# Gate_Driver_Supply.net
KiCad netlist of a schematic drawn in Altium Designer
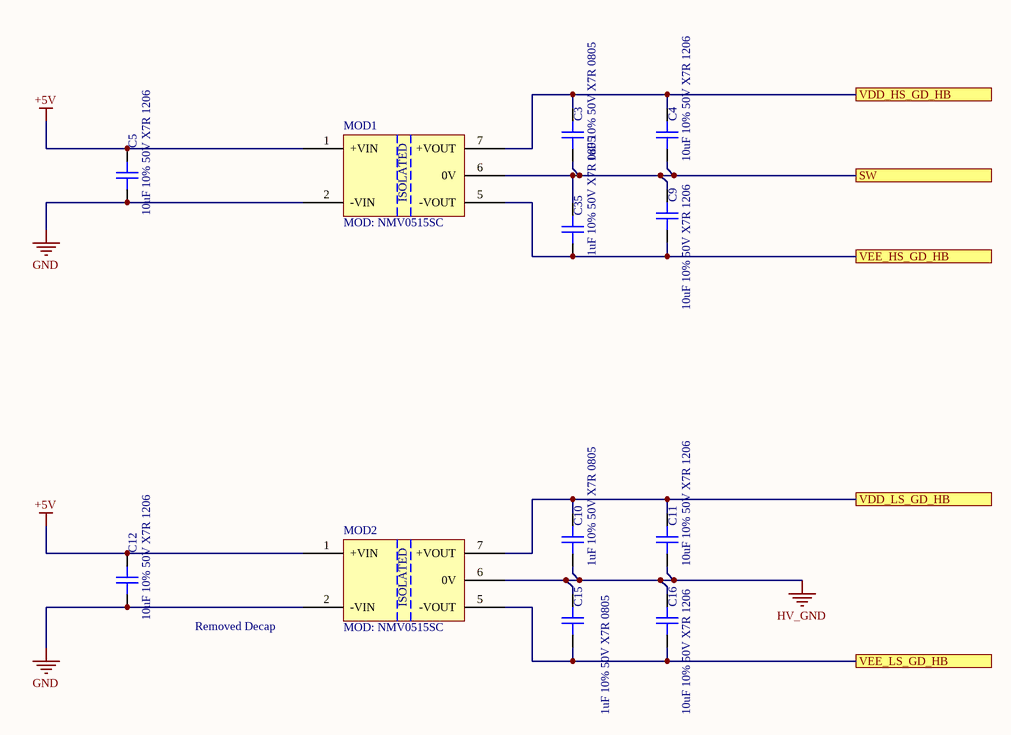
[diagram p0: Gate_Driver_Supply.SchDoc]

(export (version "E")
  (design (tool "Eeschema 10.0.6"))
  (components
    (comp (ref "C3")
      (value "1uF 10% 50V X7R 0805")
      (footprint "CAPC2012X10N")
      (fields
        (field (name "MANUFACTURER PART NUMBER") "C2012X7R1H105K125AB")
        (field (name "MANUFACTURER") "TDK")
      )
      (libsource (lib "EMEA- E-Tech Racing- I'Escola d'Enginyeria de Barcelona Est") (part "68pF 10 630V C0G 0805"))
    )
    (comp (ref "C4")
      (value "10uF 10% 50V X7R 1206")
      (footprint "CAPC3216X18N")
      (fields
        (field (name "MANUFACTURER PART NUMBER") "C3216X7R1H106K160AC")
        (field (name "MANUFACTURER") "TDK")
      )
      (libsource (lib "EMEA- E-Tech Racing- I'Escola d'Enginyeria de Barcelona Est") (part "68pF 10 630V C0G 0805"))
    )
    (comp (ref "C5")
      (value "10uF 10% 50V X7R 1206")
      (footprint "CAPC3216X18N")
      (fields
        (field (name "MANUFACTURER PART NUMBER") "C3216X7R1H106K160AC")
        (field (name "MANUFACTURER") "TDK")
      )
      (libsource (lib "EMEA- E-Tech Racing- I'Escola d'Enginyeria de Barcelona Est") (part "68pF 10 630V C0G 0805"))
    )
    (comp (ref "C9")
      (value "10uF 10% 50V X7R 1206")
      (footprint "CAPC3216X18N")
      (fields
        (field (name "MANUFACTURER PART NUMBER") "C3216X7R1H106K160AC")
        (field (name "MANUFACTURER") "TDK")
      )
      (libsource (lib "EMEA- E-Tech Racing- I'Escola d'Enginyeria de Barcelona Est") (part "68pF 10 630V C0G 0805"))
    )
    (comp (ref "C10")
      (value "1uF 10% 50V X7R 0805")
      (footprint "CAPC2012X10N")
      (fields
        (field (name "MANUFACTURER PART NUMBER") "C2012X7R1H105K125AB")
        (field (name "MANUFACTURER") "TDK")
      )
      (libsource (lib "EMEA- E-Tech Racing- I'Escola d'Enginyeria de Barcelona Est") (part "68pF 10 630V C0G 0805"))
    )
    (comp (ref "C11")
      (value "10uF 10% 50V X7R 1206")
      (footprint "CAPC3216X18N")
      (fields
        (field (name "MANUFACTURER PART NUMBER") "C3216X7R1H106K160AC")
        (field (name "MANUFACTURER") "TDK")
      )
      (libsource (lib "EMEA- E-Tech Racing- I'Escola d'Enginyeria de Barcelona Est") (part "68pF 10 630V C0G 0805"))
    )
    (comp (ref "C12")
      (value "10uF 10% 50V X7R 1206")
      (footprint "CAPC3216X18N")
      (fields
        (field (name "MANUFACTURER PART NUMBER") "C3216X7R1H106K160AC")
        (field (name "MANUFACTURER") "TDK")
      )
      (libsource (lib "EMEA- E-Tech Racing- I'Escola d'Enginyeria de Barcelona Est") (part "68pF 10 630V C0G 0805"))
    )
    (comp (ref "C15")
      (value "1uF 10% 50V X7R 0805")
      (footprint "CAPC2012X10N")
      (fields
        (field (name "MANUFACTURER PART NUMBER") "C2012X7R1H105K125AB")
        (field (name "MANUFACTURER") "TDK")
      )
      (libsource (lib "EMEA- E-Tech Racing- I'Escola d'Enginyeria de Barcelona Est") (part "68pF 10 630V C0G 0805"))
    )
    (comp (ref "C16")
      (value "10uF 10% 50V X7R 1206")
      (footprint "CAPC3216X18N")
      (fields
        (field (name "MANUFACTURER PART NUMBER") "C3216X7R1H106K160AC")
        (field (name "MANUFACTURER") "TDK")
      )
      (libsource (lib "EMEA- E-Tech Racing- I'Escola d'Enginyeria de Barcelona Est") (part "68pF 10 630V C0G 0805"))
    )
    (comp (ref "C35")
      (value "1uF 10% 50V X7R 0805")
      (footprint "CAPC2012X10N")
      (fields
        (field (name "MANUFACTURER PART NUMBER") "C2012X7R1H105K125AB")
        (field (name "MANUFACTURER") "TDK")
      )
      (libsource (lib "EMEA- E-Tech Racing- I'Escola d'Enginyeria de Barcelona Est") (part "68pF 10 630V C0G 0805"))
    )
    (comp (ref "MOD1")
      (value "MOD: NMV0515SC")
      (footprint "MOD: NMV0515SC")
      (description "Module DC-DC 5VIN 2-OUT 15V/-15V 0.033A/-0.033A 1W 5-Pin SIP Tube")
      (fields
        (field (name "MANUFACTURER") "Murata Power Solutions")
        (field (name "MANUFACTURER PART NUMBER") "NMV0515SC")
      )
      (libsource (lib "EMEA- E-Tech Racing- I'Escola d'Enginyeria de Barcelona Est") (part "MOD{colon} NMV0515SC"))
    )
    (comp (ref "MOD2")
      (value "MOD: NMV0515SC")
      (footprint "MOD: NMV0515SC")
      (description "Module DC-DC 5VIN 2-OUT 15V/-15V 0.033A/-0.033A 1W 5-Pin SIP Tube")
      (fields
        (field (name "MANUFACTURER") "Murata Power Solutions")
        (field (name "MANUFACTURER PART NUMBER") "NMV0515SC")
      )
      (libsource (lib "EMEA- E-Tech Racing- I'Escola d'Enginyeria de Barcelona Est") (part "MOD{colon} NMV0515SC"))
    )
  )
  (nets
    (net (code "1") (name "+5V") (class "Default")
      (node (ref "C12") (pin "2") (pinfunction "2_2") (pintype "passive"))
      (node (ref "C5") (pin "2") (pinfunction "2_2") (pintype "passive"))
      (node (ref "MOD1") (pin "1") (pinfunction "+VIN_1") (pintype "passive"))
      (node (ref "MOD2") (pin "1") (pinfunction "+VIN_1") (pintype "passive"))
    )
    (net (code "2") (name "/SW") (class "Default")
      (node (ref "C3") (pin "1") (pinfunction "1_1") (pintype "passive"))
      (node (ref "C35") (pin "2") (pinfunction "2_2") (pintype "passive"))
      (node (ref "C4") (pin "1") (pinfunction "1_1") (pintype "passive"))
      (node (ref "C9") (pin "2") (pinfunction "2_2") (pintype "passive"))
      (node (ref "MOD1") (pin "6") (pinfunction "0V_6") (pintype "passive"))
    )
    (net (code "3") (name "/VDD_HS_GD_HB") (class "Default")
      (node (ref "C3") (pin "2") (pinfunction "2_2") (pintype "passive"))
      (node (ref "C4") (pin "2") (pinfunction "2_2") (pintype "passive"))
      (node (ref "MOD1") (pin "7") (pinfunction "+VOUT_7") (pintype "passive"))
    )
    (net (code "4") (name "/VDD_LS_GD_HB") (class "Default")
      (node (ref "C10") (pin "2") (pinfunction "2_2") (pintype "passive"))
      (node (ref "C11") (pin "2") (pinfunction "2_2") (pintype "passive"))
      (node (ref "MOD2") (pin "7") (pinfunction "+VOUT_7") (pintype "passive"))
    )
    (net (code "5") (name "/VEE_HS_GD_HB") (class "Default")
      (node (ref "C35") (pin "1") (pinfunction "1_1") (pintype "passive"))
      (node (ref "C9") (pin "1") (pinfunction "1_1") (pintype "passive"))
      (node (ref "MOD1") (pin "5") (pinfunction "-VOUT_5") (pintype "passive"))
    )
    (net (code "6") (name "/VEE_LS_GD_HB") (class "Default")
      (node (ref "C15") (pin "1") (pinfunction "1_1") (pintype "passive"))
      (node (ref "C16") (pin "1") (pinfunction "1_1") (pintype "passive"))
      (node (ref "MOD2") (pin "5") (pinfunction "-VOUT_5") (pintype "passive"))
    )
    (net (code "7") (name "GND") (class "Default")
      (node (ref "C12") (pin "1") (pinfunction "1_1") (pintype "passive"))
      (node (ref "C5") (pin "1") (pinfunction "1_1") (pintype "passive"))
      (node (ref "MOD1") (pin "2") (pinfunction "-VIN_2") (pintype "passive"))
      (node (ref "MOD2") (pin "2") (pinfunction "-VIN_2") (pintype "passive"))
    )
    (net (code "8") (name "HV_GND") (class "Default")
      (node (ref "C10") (pin "1") (pinfunction "1_1") (pintype "passive"))
      (node (ref "C11") (pin "1") (pinfunction "1_1") (pintype "passive"))
      (node (ref "C15") (pin "2") (pinfunction "2_2") (pintype "passive"))
      (node (ref "C16") (pin "2") (pinfunction "2_2") (pintype "passive"))
      (node (ref "MOD2") (pin "6") (pinfunction "0V_6") (pintype "passive"))
    )
  )
)
